# 21_-AXEL.net
KiCad netlist of a schematic drawn in Altium Designer
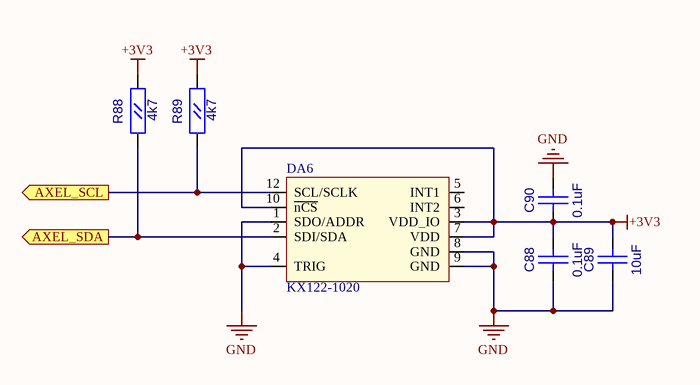
[diagram p0: [21]-AXEL.SchDoc]

(export (version "E")
  (design (tool "Eeschema 10.0.6"))
  (components
    (comp (ref "C88")
      (value "0.1uF")
      (footprint "CC0603")
      (description "CC0603")
      (libsource (lib "fizik_lib") (part "CC0603"))
    )
    (comp (ref "C89")
      (value "10uF")
      (footprint "CC0805")
      (description "CC0805")
      (libsource (lib "fizik_lib") (part "CC0805"))
    )
    (comp (ref "C90")
      (value "0.1uF")
      (footprint "CC0603")
      (description "CC0603")
      (libsource (lib "fizik_lib") (part "CC0603"))
    )
    (comp (ref "DA6")
      (value "KX122-1020")
      (footprint "LGA-12")
      (libsource (lib "fizik_lib") (part "KX022-1020"))
    )
    (comp (ref "R88")
      (value "4k7")
      (footprint "RC0603")
      (description "RC0603")
      (libsource (lib "fizik_lib") (part "RC0603"))
    )
    (comp (ref "R89")
      (value "4k7")
      (footprint "RC0603")
      (description "RC0603")
      (libsource (lib "fizik_lib") (part "RC0603"))
    )
  )
  (nets
    (net (code "1") (name "+3V3") (class "Default")
      (node (ref "C88") (pin "2") (pinfunction "B_2") (pintype "passive"))
      (node (ref "C89") (pin "2") (pinfunction "B_2") (pintype "passive"))
      (node (ref "C90") (pin "1") (pinfunction "A_1") (pintype "passive"))
      (node (ref "DA6") (pin "10") (pinfunction "~{nCS}_10") (pintype "passive"))
      (node (ref "DA6") (pin "3") (pinfunction "VDD_IO_3") (pintype "passive"))
      (node (ref "DA6") (pin "7") (pinfunction "VDD_7") (pintype "passive"))
      (node (ref "R88") (pin "2") (pinfunction "B_2") (pintype "passive"))
      (node (ref "R89") (pin "2") (pinfunction "B_2") (pintype "passive"))
    )
    (net (code "2") (name "/AXEL_SCL") (class "Default")
      (node (ref "DA6") (pin "12") (pinfunction "SCL/SCLK_12") (pintype "passive"))
      (node (ref "R89") (pin "1") (pinfunction "A_1") (pintype "passive"))
    )
    (net (code "3") (name "/AXEL_SDA") (class "Default")
      (node (ref "DA6") (pin "2") (pinfunction "SDI/SDA_2") (pintype "passive"))
      (node (ref "R88") (pin "1") (pinfunction "A_1") (pintype "passive"))
    )
    (net (code "4") (name "GND") (class "Default")
      (node (ref "C88") (pin "1") (pinfunction "A_1") (pintype "passive"))
      (node (ref "C89") (pin "1") (pinfunction "A_1") (pintype "passive"))
      (node (ref "C90") (pin "2") (pinfunction "B_2") (pintype "passive"))
      (node (ref "DA6") (pin "1") (pinfunction "SDO/ADDR_1") (pintype "passive"))
      (node (ref "DA6") (pin "4") (pinfunction "TRIG_4") (pintype "passive"))
      (node (ref "DA6") (pin "8") (pinfunction "GND_8") (pintype "passive"))
      (node (ref "DA6") (pin "9") (pinfunction "GND_9") (pintype "passive"))
    )
    (net (code "5") (name "unconnected-(DA6-INT1-Pad5)") (class "Default")
      (node (ref "DA6") (pin "5") (pinfunction "INT1_5") (pintype "passive"))
    )
    (net (code "6") (name "unconnected-(DA6-INT2-Pad6)") (class "Default")
      (node (ref "DA6") (pin "6") (pinfunction "INT2_6") (pintype "passive"))
    )
  )
)
